# Placa_ATMEL_2019_v2_4.net
KiCad netlist of a schematic drawn in EAGLE
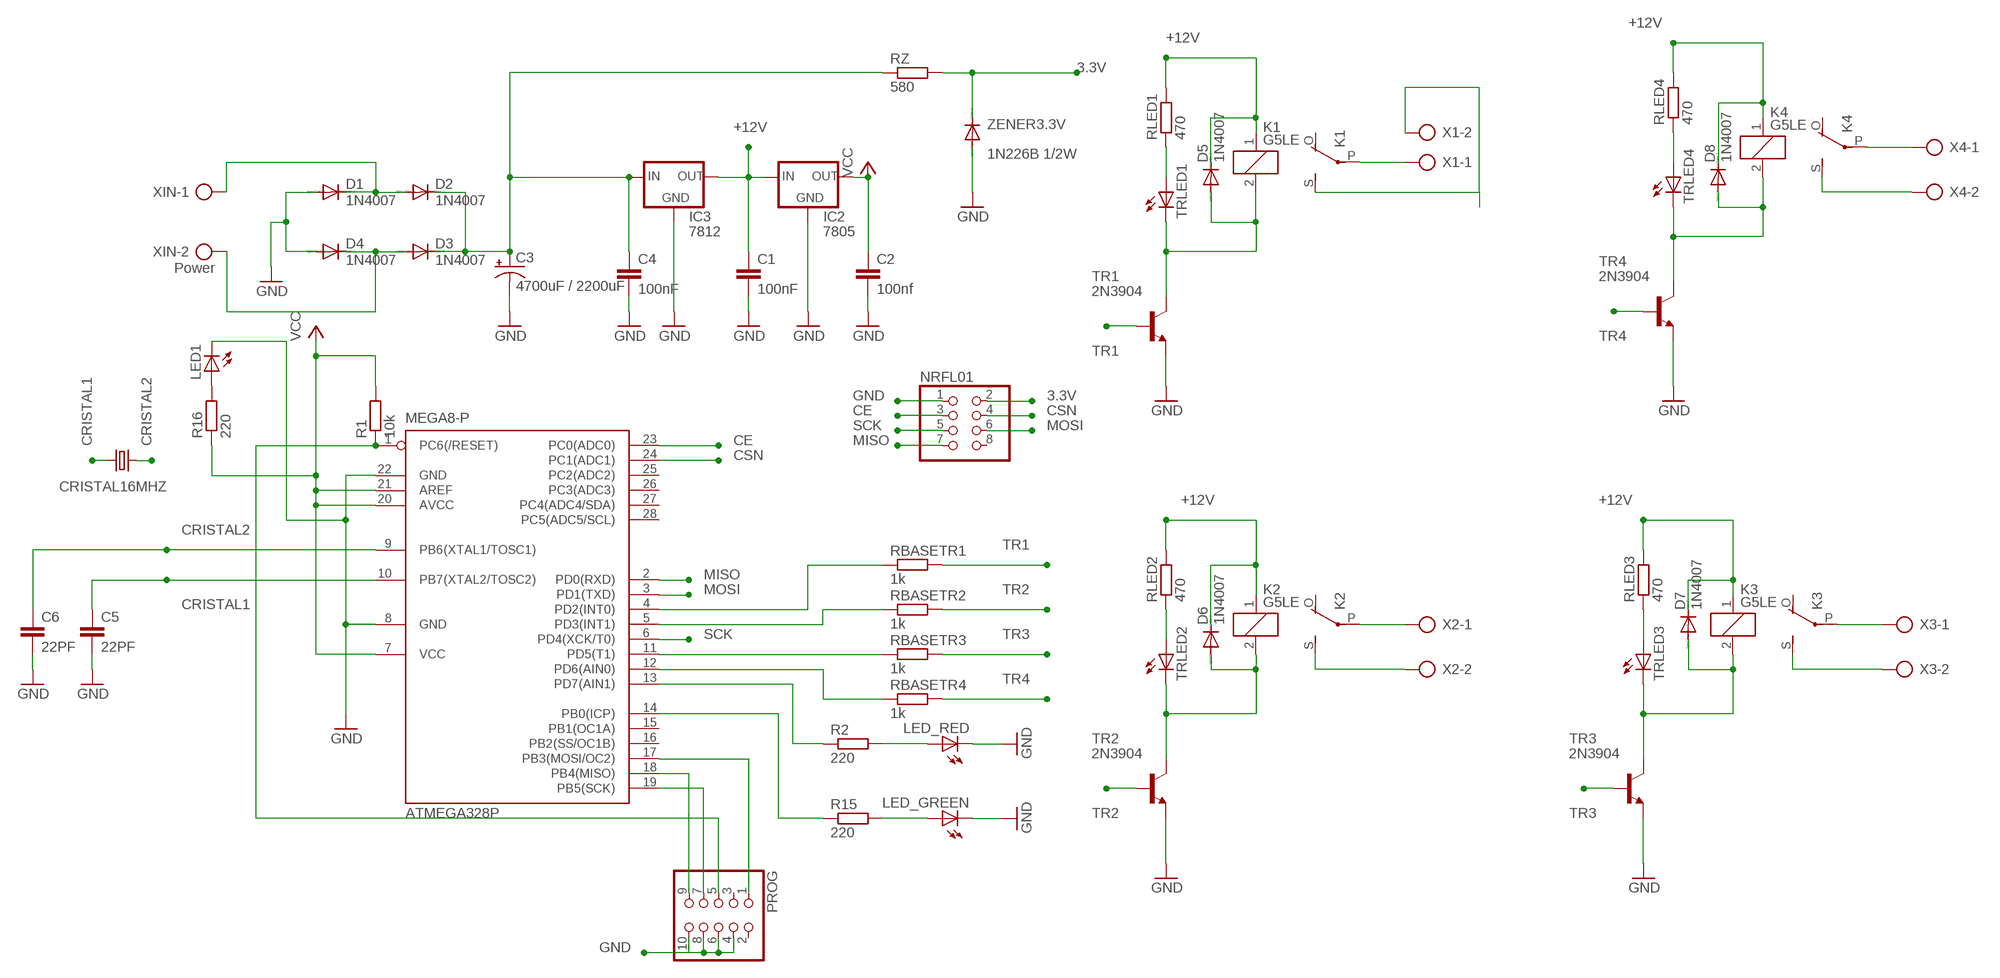
[diagram p0: schematic, sheet 1]

(export (version "E")
  (design (tool "Eeschema 10.0.6"))
  (components
    (comp (ref "ATMEGA328P")
      (value "MEGA8-P")
      (footprint "eagle-import:DIL28-3")
      (libsource (lib "eagle-import") (part "MEGA8-P"))
    )
    (comp (ref "C1")
      (value "100nF")
      (footprint "eagle-import:C050-025X075")
      (libsource (lib "eagle-import") (part "C-EU050-025X075"))
    )
    (comp (ref "C2")
      (value "100nf")
      (footprint "eagle-import:C050-025X075")
      (libsource (lib "eagle-import") (part "C-EU050-025X075"))
    )
    (comp (ref "C3")
      (value "4700uF / 2200uF")
      (footprint "eagle-import:E7,5-16")
      (libsource (lib "eagle-import") (part "CPOL-USE7.5-16"))
    )
    (comp (ref "C4")
      (value "100nF")
      (footprint "eagle-import:C050-025X075")
      (libsource (lib "eagle-import") (part "C-EU050-025X075"))
    )
    (comp (ref "C5")
      (value "22PF")
      (footprint "eagle-import:C050-024X044")
      (libsource (lib "eagle-import") (part "C-EU050-024X044"))
    )
    (comp (ref "C6")
      (value "22PF")
      (footprint "eagle-import:C050-024X044")
      (libsource (lib "eagle-import") (part "C-EU050-024X044"))
    )
    (comp (ref "CRISTAL16MHZ")
      (value "CRYSTALHC49S")
      (footprint "eagle-import:HC49_S")
      (libsource (lib "eagle-import") (part "CRYSTALHC49S"))
    )
    (comp (ref "D1")
      (value "1N4007")
      (footprint "eagle-import:DO41-10")
      (libsource (lib "eagle-import") (part "1N4004"))
    )
    (comp (ref "D2")
      (value "1N4007")
      (footprint "eagle-import:DO41-10")
      (libsource (lib "eagle-import") (part "1N4004"))
    )
    (comp (ref "D3")
      (value "1N4007")
      (footprint "eagle-import:DO41-10")
      (libsource (lib "eagle-import") (part "1N4004"))
    )
    (comp (ref "D4")
      (value "1N4007")
      (footprint "eagle-import:DO41-10")
      (libsource (lib "eagle-import") (part "1N4004"))
    )
    (comp (ref "D5")
      (value "1N4007")
      (footprint "eagle-import:DO41-10")
      (libsource (lib "eagle-import") (part "1N4004"))
    )
    (comp (ref "D6")
      (value "1N4007")
      (footprint "eagle-import:DO41-10")
      (libsource (lib "eagle-import") (part "1N4004"))
    )
    (comp (ref "D7")
      (value "1N4007")
      (footprint "eagle-import:DO41-10")
      (libsource (lib "eagle-import") (part "1N4004"))
    )
    (comp (ref "D8")
      (value "1N4007")
      (footprint "eagle-import:DO41-10")
      (libsource (lib "eagle-import") (part "1N4004"))
    )
    (comp (ref "IC2")
      (value "7805")
      (footprint "eagle-import:78XXL")
      (libsource (lib "eagle-import") (part "78XXL"))
    )
    (comp (ref "IC3")
      (value "7812")
      (footprint "eagle-import:78XXL")
      (libsource (lib "eagle-import") (part "78XXL"))
    )
    (comp (ref "K1")
      (value "G5LE")
      (footprint "eagle-import:G5LE")
      (libsource (lib "eagle-import") (part "G5LE"))
    )
    (comp (ref "K2")
      (value "G5LE")
      (footprint "eagle-import:G5LE")
      (libsource (lib "eagle-import") (part "G5LE"))
    )
    (comp (ref "K3")
      (value "G5LE")
      (footprint "eagle-import:G5LE")
      (libsource (lib "eagle-import") (part "G5LE"))
    )
    (comp (ref "K4")
      (value "G5LE")
      (footprint "eagle-import:G5LE")
      (libsource (lib "eagle-import") (part "G5LE"))
    )
    (comp (ref "LED1")
      (value "LED5MM")
      (footprint "eagle-import:LED5MM")
      (libsource (lib "eagle-import") (part "LED5MM"))
    )
    (comp (ref "LED_GREEN")
      (value "LED5MM")
      (footprint "eagle-import:LED5MM")
      (libsource (lib "eagle-import") (part "LED5MM"))
    )
    (comp (ref "LED_RED")
      (value "LED5MM")
      (footprint "eagle-import:LED5MM")
      (libsource (lib "eagle-import") (part "LED5MM"))
    )
    (comp (ref "NRFL01")
      (value "PINHD-2X4")
      (footprint "eagle-import:2X04")
      (libsource (lib "eagle-import") (part "PINHD-2X4"))
    )
    (comp (ref "PROG")
      (value "PINHD-2X5")
      (footprint "eagle-import:2X05")
      (libsource (lib "eagle-import") (part "PINHD-2X5"))
    )
    (comp (ref "R1")
      (value "10k")
      (footprint "eagle-import:0207_10")
      (libsource (lib "eagle-import") (part "R-EU_0207/10"))
    )
    (comp (ref "R2")
      (value "220")
      (footprint "eagle-import:0207_10")
      (libsource (lib "eagle-import") (part "R-EU_0207/10"))
    )
    (comp (ref "R15")
      (value "220")
      (footprint "eagle-import:0207_10")
      (libsource (lib "eagle-import") (part "R-EU_0207/10"))
    )
    (comp (ref "R16")
      (value "220")
      (footprint "eagle-import:0309_10")
      (libsource (lib "eagle-import") (part "R-EU_0309/10"))
    )
    (comp (ref "RBASETR1")
      (value "1k")
      (footprint "eagle-import:0207_10")
      (libsource (lib "eagle-import") (part "R-EU_0207/10"))
    )
    (comp (ref "RBASETR2")
      (value "1k")
      (footprint "eagle-import:0207_10")
      (libsource (lib "eagle-import") (part "R-EU_0207/10"))
    )
    (comp (ref "RBASETR3")
      (value "1k")
      (footprint "eagle-import:0204_7")
      (libsource (lib "eagle-import") (part "R-EU_0204/7"))
    )
    (comp (ref "RBASETR4")
      (value "1k")
      (footprint "eagle-import:0207_15")
      (libsource (lib "eagle-import") (part "R-EU_0207/15"))
    )
    (comp (ref "RLED1")
      (value "470")
      (footprint "eagle-import:0207_10")
      (libsource (lib "eagle-import") (part "R-EU_0207/10"))
    )
    (comp (ref "RLED2")
      (value "470")
      (footprint "eagle-import:0207_10")
      (libsource (lib "eagle-import") (part "R-EU_0207/10"))
    )
    (comp (ref "RLED3")
      (value "470")
      (footprint "eagle-import:0207_10")
      (libsource (lib "eagle-import") (part "R-EU_0207/10"))
    )
    (comp (ref "RLED4")
      (value "470")
      (footprint "eagle-import:0207_10")
      (libsource (lib "eagle-import") (part "R-EU_0207/10"))
    )
    (comp (ref "RZ")
      (value "580")
      (footprint "eagle-import:0207_10")
      (libsource (lib "eagle-import") (part "R-EU_0207/10"))
    )
    (comp (ref "TR1")
      (value "2N3904")
      (footprint "eagle-import:TO92")
      (libsource (lib "eagle-import") (part "2N3904"))
    )
    (comp (ref "TR2")
      (value "2N3904")
      (footprint "eagle-import:TO92")
      (libsource (lib "eagle-import") (part "2N3904"))
    )
    (comp (ref "TR3")
      (value "2N3904")
      (footprint "eagle-import:TO92")
      (libsource (lib "eagle-import") (part "2N3904"))
    )
    (comp (ref "TR4")
      (value "2N3904")
      (footprint "eagle-import:TO92")
      (libsource (lib "eagle-import") (part "2N3904"))
    )
    (comp (ref "TRLED1")
      (value "LED5MM")
      (footprint "eagle-import:LED5MM")
      (libsource (lib "eagle-import") (part "LED5MM"))
    )
    (comp (ref "TRLED2")
      (value "LED5MM")
      (footprint "eagle-import:LED5MM")
      (libsource (lib "eagle-import") (part "LED5MM"))
    )
    (comp (ref "TRLED3")
      (value "LED5MM")
      (footprint "eagle-import:LED5MM")
      (libsource (lib "eagle-import") (part "LED5MM"))
    )
    (comp (ref "TRLED4")
      (value "LED5MM")
      (footprint "eagle-import:LED5MM")
      (libsource (lib "eagle-import") (part "LED5MM"))
    )
    (comp (ref "X1")
      (value "AK300/2")
      (footprint "eagle-import:AK300_2")
      (libsource (lib "eagle-import") (part "AK300/2"))
    )
    (comp (ref "X2")
      (value "AK300/2")
      (footprint "eagle-import:AK300_2")
      (libsource (lib "eagle-import") (part "AK300/2"))
    )
    (comp (ref "X3")
      (value "AK300/2")
      (footprint "eagle-import:AK300_2")
      (libsource (lib "eagle-import") (part "AK300/2"))
    )
    (comp (ref "X4")
      (value "AK300/2")
      (footprint "eagle-import:AK300_2")
      (libsource (lib "eagle-import") (part "AK300/2"))
    )
    (comp (ref "XIN")
      (value "Power")
      (footprint "eagle-import:AK500_2")
      (libsource (lib "eagle-import") (part "AK500/2"))
    )
    (comp (ref "ZENER3.3V")
      (value "1N226B 1/2W")
      (footprint "eagle-import:DO35-10")
      (libsource (lib "eagle-import") (part "1N4148DO35-10"))
    )
  )
  (nets
    (net (code "1") (name "/+12V") (class "Default")
      (node (ref "C1") (pin "1") (pinfunction "1_1") (pintype "passive"))
      (node (ref "D5") (pin "C") (pinfunction "C_C") (pintype "passive"))
      (node (ref "D6") (pin "C") (pinfunction "C_C") (pintype "passive"))
      (node (ref "D7") (pin "C") (pinfunction "C_C") (pintype "passive"))
      (node (ref "D8") (pin "C") (pinfunction "C_C") (pintype "passive"))
      (node (ref "IC2") (pin "IN") (pinfunction "IN_IN") (pintype "input"))
      (node (ref "IC3") (pin "OUT") (pinfunction "OUT_OUT") (pintype "passive"))
      (node (ref "K1") (pin "1") (pinfunction "1_1") (pintype "passive"))
      (node (ref "K2") (pin "1") (pinfunction "1_1") (pintype "passive"))
      (node (ref "K3") (pin "1") (pinfunction "1_1") (pintype "passive"))
      (node (ref "K4") (pin "1") (pinfunction "1_1") (pintype "passive"))
      (node (ref "RLED1") (pin "2") (pinfunction "2_2") (pintype "passive"))
      (node (ref "RLED2") (pin "2") (pinfunction "2_2") (pintype "passive"))
      (node (ref "RLED3") (pin "2") (pinfunction "2_2") (pintype "passive"))
      (node (ref "RLED4") (pin "2") (pinfunction "2_2") (pintype "passive"))
    )
    (net (code "2") (name "/3.3V") (class "Default")
      (node (ref "NRFL01") (pin "2") (pinfunction "2_2") (pintype "passive"))
      (node (ref "RZ") (pin "2") (pinfunction "2_2") (pintype "passive"))
      (node (ref "ZENER3.3V") (pin "C") (pinfunction "C_C") (pintype "passive"))
    )
    (net (code "3") (name "/CE") (class "Default")
      (node (ref "ATMEGA328P") (pin "23") (pinfunction "PC0(ADC0)_23") (pintype "bidirectional"))
      (node (ref "NRFL01") (pin "3") (pinfunction "3_3") (pintype "passive"))
    )
    (net (code "4") (name "/CRISTAL1") (class "Default")
      (node (ref "ATMEGA328P") (pin "10") (pinfunction "PB7(XTAL2/TOSC2)_10") (pintype "bidirectional"))
      (node (ref "C5") (pin "1") (pinfunction "1_1") (pintype "passive"))
      (node (ref "CRISTAL16MHZ") (pin "2") (pinfunction "2_2") (pintype "passive"))
    )
    (net (code "5") (name "/CRISTAL2") (class "Default")
      (node (ref "ATMEGA328P") (pin "9") (pinfunction "PB6(XTAL1/TOSC1)_9") (pintype "bidirectional"))
      (node (ref "C6") (pin "1") (pinfunction "1_1") (pintype "passive"))
      (node (ref "CRISTAL16MHZ") (pin "1") (pinfunction "1_1") (pintype "passive"))
    )
    (net (code "6") (name "/CSN") (class "Default")
      (node (ref "ATMEGA328P") (pin "24") (pinfunction "PC1(ADC1)_24") (pintype "bidirectional"))
      (node (ref "NRFL01") (pin "4") (pinfunction "4_4") (pintype "passive"))
    )
    (net (code "7") (name "/MISO") (class "Default")
      (node (ref "ATMEGA328P") (pin "2") (pinfunction "PD0(RXD)_2") (pintype "bidirectional"))
      (node (ref "NRFL01") (pin "7") (pinfunction "7_7") (pintype "passive"))
    )
    (net (code "8") (name "/MOSI") (class "Default")
      (node (ref "ATMEGA328P") (pin "3") (pinfunction "PD1(TXD)_3") (pintype "bidirectional"))
      (node (ref "NRFL01") (pin "6") (pinfunction "6_6") (pintype "passive"))
    )
    (net (code "9") (name "/SCK") (class "Default")
      (node (ref "ATMEGA328P") (pin "6") (pinfunction "PD4(XCK/T0)_6") (pintype "bidirectional"))
      (node (ref "NRFL01") (pin "5") (pinfunction "5_5") (pintype "passive"))
    )
    (net (code "10") (name "/TR1") (class "Default")
      (node (ref "RBASETR1") (pin "2") (pinfunction "2_2") (pintype "passive"))
      (node (ref "TR1") (pin "2") (pinfunction "B_2") (pintype "passive"))
    )
    (net (code "11") (name "/TR2") (class "Default")
      (node (ref "RBASETR2") (pin "2") (pinfunction "2_2") (pintype "passive"))
      (node (ref "TR2") (pin "2") (pinfunction "B_2") (pintype "passive"))
    )
    (net (code "12") (name "/TR3") (class "Default")
      (node (ref "RBASETR3") (pin "2") (pinfunction "2_2") (pintype "passive"))
      (node (ref "TR3") (pin "2") (pinfunction "B_2") (pintype "passive"))
    )
    (net (code "13") (name "/TR4") (class "Default")
      (node (ref "RBASETR4") (pin "2") (pinfunction "2_2") (pintype "passive"))
      (node (ref "TR4") (pin "2") (pinfunction "B_2") (pintype "passive"))
    )
    (net (code "14") (name "GND") (class "Default")
      (node (ref "ATMEGA328P") (pin "22") (pinfunction "GND_22") (pintype "power_in"))
      (node (ref "ATMEGA328P") (pin "8") (pinfunction "GND_8") (pintype "power_in"))
      (node (ref "C1") (pin "2") (pinfunction "2_2") (pintype "passive"))
      (node (ref "C2") (pin "2") (pinfunction "2_2") (pintype "passive"))
      (node (ref "C3") (pin "-") (pinfunction "-_-") (pintype "passive"))
      (node (ref "C4") (pin "2") (pinfunction "2_2") (pintype "passive"))
      (node (ref "C5") (pin "2") (pinfunction "2_2") (pintype "passive"))
      (node (ref "C6") (pin "2") (pinfunction "2_2") (pintype "passive"))
      (node (ref "D1") (pin "A") (pinfunction "A_A") (pintype "passive"))
      (node (ref "D4") (pin "A") (pinfunction "A_A") (pintype "passive"))
      (node (ref "IC2") (pin "GND") (pinfunction "GND_GND") (pintype "input"))
      (node (ref "IC3") (pin "GND") (pinfunction "GND_GND") (pintype "input"))
      (node (ref "LED1") (pin "K") (pinfunction "C_K") (pintype "passive"))
      (node (ref "LED_GREEN") (pin "K") (pinfunction "C_K") (pintype "passive"))
      (node (ref "LED_RED") (pin "K") (pinfunction "C_K") (pintype "passive"))
      (node (ref "NRFL01") (pin "1") (pinfunction "1_1") (pintype "passive"))
      (node (ref "PROG") (pin "10") (pinfunction "10_10") (pintype "passive"))
      (node (ref "PROG") (pin "4") (pinfunction "4_4") (pintype "passive"))
      (node (ref "PROG") (pin "6") (pinfunction "6_6") (pintype "passive"))
      (node (ref "PROG") (pin "8") (pinfunction "8_8") (pintype "passive"))
      (node (ref "TR1") (pin "3") (pinfunction "E_3") (pintype "passive"))
      (node (ref "TR2") (pin "3") (pinfunction "E_3") (pintype "passive"))
      (node (ref "TR3") (pin "3") (pinfunction "E_3") (pintype "passive"))
      (node (ref "TR4") (pin "3") (pinfunction "E_3") (pintype "passive"))
      (node (ref "ZENER3.3V") (pin "A") (pinfunction "A_A") (pintype "passive"))
    )
    (net (code "15") (name "Net-(ATMEGA328P-PB0(ICP))") (class "Default")
      (node (ref "ATMEGA328P") (pin "14") (pinfunction "PB0(ICP)_14") (pintype "bidirectional"))
      (node (ref "R15") (pin "1") (pinfunction "1_1") (pintype "passive"))
    )
    (net (code "16") (name "Net-(ATMEGA328P-PB3(MOSI{slash}OC2))") (class "Default")
      (node (ref "ATMEGA328P") (pin "17") (pinfunction "PB3(MOSI/OC2)_17") (pintype "bidirectional"))
      (node (ref "PROG") (pin "1") (pinfunction "1_1") (pintype "passive"))
    )
    (net (code "17") (name "Net-(ATMEGA328P-PB4(MISO))") (class "Default")
      (node (ref "ATMEGA328P") (pin "18") (pinfunction "PB4(MISO)_18") (pintype "bidirectional"))
      (node (ref "PROG") (pin "9") (pinfunction "9_9") (pintype "passive"))
    )
    (net (code "18") (name "Net-(ATMEGA328P-PB5(SCK))") (class "Default")
      (node (ref "ATMEGA328P") (pin "19") (pinfunction "PB5(SCK)_19") (pintype "bidirectional"))
      (node (ref "PROG") (pin "7") (pinfunction "7_7") (pintype "passive"))
    )
    (net (code "19") (name "Net-(ATMEGA328P-PC6({slash}RESET))") (class "Default")
      (node (ref "ATMEGA328P") (pin "1") (pinfunction "PC6(/RESET)_1") (pintype "bidirectional"))
      (node (ref "PROG") (pin "5") (pinfunction "5_5") (pintype "passive"))
      (node (ref "R1") (pin "1") (pinfunction "1_1") (pintype "passive"))
    )
    (net (code "20") (name "Net-(ATMEGA328P-PD2(INT0))") (class "Default")
      (node (ref "ATMEGA328P") (pin "4") (pinfunction "PD2(INT0)_4") (pintype "bidirectional"))
      (node (ref "RBASETR1") (pin "1") (pinfunction "1_1") (pintype "passive"))
    )
    (net (code "21") (name "Net-(ATMEGA328P-PD3(INT1))") (class "Default")
      (node (ref "ATMEGA328P") (pin "5") (pinfunction "PD3(INT1)_5") (pintype "bidirectional"))
      (node (ref "RBASETR2") (pin "1") (pinfunction "1_1") (pintype "passive"))
    )
    (net (code "22") (name "Net-(ATMEGA328P-PD5(T1))") (class "Default")
      (node (ref "ATMEGA328P") (pin "11") (pinfunction "PD5(T1)_11") (pintype "bidirectional"))
      (node (ref "RBASETR3") (pin "1") (pinfunction "1_1") (pintype "passive"))
    )
    (net (code "23") (name "Net-(ATMEGA328P-PD6(AIN0))") (class "Default")
      (node (ref "ATMEGA328P") (pin "12") (pinfunction "PD6(AIN0)_12") (pintype "bidirectional"))
      (node (ref "RBASETR4") (pin "1") (pinfunction "1_1") (pintype "passive"))
    )
    (net (code "24") (name "Net-(ATMEGA328P-PD7(AIN1))") (class "Default")
      (node (ref "ATMEGA328P") (pin "13") (pinfunction "PD7(AIN1)_13") (pintype "bidirectional"))
      (node (ref "R2") (pin "1") (pinfunction "1_1") (pintype "passive"))
    )
    (net (code "25") (name "Net-(C3-Pad+)") (class "Default")
      (node (ref "C3") (pin "+") (pinfunction "+_+") (pintype "passive"))
      (node (ref "C4") (pin "1") (pinfunction "1_1") (pintype "passive"))
      (node (ref "D2") (pin "C") (pinfunction "C_C") (pintype "passive"))
      (node (ref "D3") (pin "C") (pinfunction "C_C") (pintype "passive"))
      (node (ref "IC3") (pin "IN") (pinfunction "IN_IN") (pintype "input"))
      (node (ref "RZ") (pin "1") (pinfunction "1_1") (pintype "passive"))
    )
    (net (code "26") (name "Net-(LED1-PadA)") (class "Default")
      (node (ref "LED1") (pin "A") (pinfunction "A_A") (pintype "passive"))
      (node (ref "R16") (pin "2") (pinfunction "2_2") (pintype "passive"))
    )
    (net (code "27") (name "Net-(LED_GREEN-PadA)") (class "Default")
      (node (ref "LED_GREEN") (pin "A") (pinfunction "A_A") (pintype "passive"))
      (node (ref "R15") (pin "2") (pinfunction "2_2") (pintype "passive"))
    )
    (net (code "28") (name "Net-(LED_RED-PadA)") (class "Default")
      (node (ref "LED_RED") (pin "A") (pinfunction "A_A") (pintype "passive"))
      (node (ref "R2") (pin "2") (pinfunction "2_2") (pintype "passive"))
    )
    (net (code "29") (name "Net-(RLED1-Pad1)") (class "Default")
      (node (ref "RLED1") (pin "1") (pinfunction "1_1") (pintype "passive"))
      (node (ref "TRLED1") (pin "A") (pinfunction "A_A") (pintype "passive"))
    )
    (net (code "30") (name "Net-(RLED2-Pad1)") (class "Default")
      (node (ref "RLED2") (pin "1") (pinfunction "1_1") (pintype "passive"))
      (node (ref "TRLED2") (pin "A") (pinfunction "A_A") (pintype "passive"))
    )
    (net (code "31") (name "Net-(RLED3-Pad1)") (class "Default")
      (node (ref "RLED3") (pin "1") (pinfunction "1_1") (pintype "passive"))
      (node (ref "TRLED3") (pin "A") (pinfunction "A_A") (pintype "passive"))
    )
    (net (code "32") (name "Net-(RLED4-Pad1)") (class "Default")
      (node (ref "RLED4") (pin "1") (pinfunction "1_1") (pintype "passive"))
      (node (ref "TRLED4") (pin "A") (pinfunction "A_A") (pintype "passive"))
    )
    (net (code "33") (name "Net-(TR1-C)") (class "Default")
      (node (ref "D5") (pin "A") (pinfunction "A_A") (pintype "passive"))
      (node (ref "K1") (pin "2") (pinfunction "2_2") (pintype "passive"))
      (node (ref "TR1") (pin "1") (pinfunction "C_1") (pintype "passive"))
      (node (ref "TRLED1") (pin "K") (pinfunction "C_K") (pintype "passive"))
    )
    (net (code "34") (name "Net-(TR2-C)") (class "Default")
      (node (ref "D6") (pin "A") (pinfunction "A_A") (pintype "passive"))
      (node (ref "K2") (pin "2") (pinfunction "2_2") (pintype "passive"))
      (node (ref "TR2") (pin "1") (pinfunction "C_1") (pintype "passive"))
      (node (ref "TRLED2") (pin "K") (pinfunction "C_K") (pintype "passive"))
    )
    (net (code "35") (name "Net-(TR3-C)") (class "Default")
      (node (ref "D7") (pin "A") (pinfunction "A_A") (pintype "passive"))
      (node (ref "K3") (pin "2") (pinfunction "2_2") (pintype "passive"))
      (node (ref "TR3") (pin "1") (pinfunction "C_1") (pintype "passive"))
      (node (ref "TRLED3") (pin "K") (pinfunction "C_K") (pintype "passive"))
    )
    (net (code "36") (name "Net-(TR4-C)") (class "Default")
      (node (ref "D8") (pin "A") (pinfunction "A_A") (pintype "passive"))
      (node (ref "K4") (pin "2") (pinfunction "2_2") (pintype "passive"))
      (node (ref "TR4") (pin "1") (pinfunction "C_1") (pintype "passive"))
      (node (ref "TRLED4") (pin "K") (pinfunction "C_K") (pintype "passive"))
    )
    (net (code "37") (name "Net-(X1A-KL)") (class "Default")
      (node (ref "K1") (pin "P") (pinfunction "P_P") (pintype "passive"))
      (node (ref "X1") (pin "1") (pinfunction "KL_1") (pintype "passive"))
    )
    (net (code "38") (name "Net-(X1B-KL)") (class "Default")
      (node (ref "K1") (pin "S") (pinfunction "S_S") (pintype "passive"))
      (node (ref "X1") (pin "2") (pinfunction "KL_2") (pintype "passive"))
    )
    (net (code "39") (name "Net-(X2A-KL)") (class "Default")
      (node (ref "K2") (pin "P") (pinfunction "P_P") (pintype "passive"))
      (node (ref "X2") (pin "1") (pinfunction "KL_1") (pintype "passive"))
    )
    (net (code "40") (name "Net-(X2B-KL)") (class "Default")
      (node (ref "K2") (pin "S") (pinfunction "S_S") (pintype "passive"))
      (node (ref "X2") (pin "2") (pinfunction "KL_2") (pintype "passive"))
    )
    (net (code "41") (name "Net-(X3A-KL)") (class "Default")
      (node (ref "K3") (pin "P") (pinfunction "P_P") (pintype "passive"))
      (node (ref "X3") (pin "1") (pinfunction "KL_1") (pintype "passive"))
    )
    (net (code "42") (name "Net-(X3B-KL)") (class "Default")
      (node (ref "K3") (pin "S") (pinfunction "S_S") (pintype "passive"))
      (node (ref "X3") (pin "2") (pinfunction "KL_2") (pintype "passive"))
    )
    (net (code "43") (name "Net-(X4A-KL)") (class "Default")
      (node (ref "K4") (pin "P") (pinfunction "P_P") (pintype "passive"))
      (node (ref "X4") (pin "1") (pinfunction "KL_1") (pintype "passive"))
    )
    (net (code "44") (name "Net-(X4B-KL)") (class "Default")
      (node (ref "K4") (pin "S") (pinfunction "S_S") (pintype "passive"))
      (node (ref "X4") (pin "2") (pinfunction "KL_2") (pintype "passive"))
    )
    (net (code "45") (name "Net-(XINA-KL)") (class "Default")
      (node (ref "D1") (pin "C") (pinfunction "C_C") (pintype "passive"))
      (node (ref "D2") (pin "A") (pinfunction "A_A") (pintype "passive"))
      (node (ref "XIN") (pin "1") (pinfunction "KL_1") (pintype "passive"))
    )
    (net (code "46") (name "Net-(XINB-KL)") (class "Default")
      (node (ref "D3") (pin "A") (pinfunction "A_A") (pintype "passive"))
      (node (ref "D4") (pin "C") (pinfunction "C_C") (pintype "passive"))
      (node (ref "XIN") (pin "2") (pinfunction "KL_2") (pintype "passive"))
    )
    (net (code "47") (name "VCC") (class "Default")
      (node (ref "ATMEGA328P") (pin "20") (pinfunction "AVCC_20") (pintype "power_in"))
      (node (ref "ATMEGA328P") (pin "21") (pinfunction "AREF_21") (pintype "passive"))
      (node (ref "ATMEGA328P") (pin "7") (pinfunction "VCC_7") (pintype "power_in"))
      (node (ref "C2") (pin "1") (pinfunction "1_1") (pintype "passive"))
      (node (ref "IC2") (pin "OUT") (pinfunction "OUT_OUT") (pintype "passive"))
      (node (ref "R1") (pin "2") (pinfunction "2_2") (pintype "passive"))
      (node (ref "R16") (pin "1") (pinfunction "1_1") (pintype "passive"))
    )
    (net (code "48") (name "unconnected-(ATMEGA328P-PB1(OC1A)-Pad15)") (class "Default")
      (node (ref "ATMEGA328P") (pin "15") (pinfunction "PB1(OC1A)_15") (pintype "bidirectional"))
    )
    (net (code "49") (name "unconnected-(ATMEGA328P-PB2(SS{slash}OC1B)-Pad16)") (class "Default")
      (node (ref "ATMEGA328P") (pin "16") (pinfunction "PB2(SS/OC1B)_16") (pintype "bidirectional"))
    )
    (net (code "50") (name "unconnected-(ATMEGA328P-PC2(ADC2)-Pad25)") (class "Default")
      (node (ref "ATMEGA328P") (pin "25") (pinfunction "PC2(ADC2)_25") (pintype "bidirectional"))
    )
    (net (code "51") (name "unconnected-(ATMEGA328P-PC3(ADC3)-Pad26)") (class "Default")
      (node (ref "ATMEGA328P") (pin "26") (pinfunction "PC3(ADC3)_26") (pintype "bidirectional"))
    )
    (net (code "52") (name "unconnected-(ATMEGA328P-PC4(ADC4{slash}SDA)-Pad27)") (class "Default")
      (node (ref "ATMEGA328P") (pin "27") (pinfunction "PC4(ADC4/SDA)_27") (pintype "bidirectional"))
    )
    (net (code "53") (name "unconnected-(ATMEGA328P-PC5(ADC5{slash}SCL)-Pad28)") (class "Default")
      (node (ref "ATMEGA328P") (pin "28") (pinfunction "PC5(ADC5/SCL)_28") (pintype "bidirectional"))
    )
    (net (code "54") (name "unconnected-(K1-PadO)") (class "Default")
      (node (ref "K1") (pin "O") (pinfunction "O_O") (pintype "passive"))
    )
    (net (code "55") (name "unconnected-(K2-PadO)") (class "Default")
      (node (ref "K2") (pin "O") (pinfunction "O_O") (pintype "passive"))
    )
    (net (code "56") (name "unconnected-(K3-PadO)") (class "Default")
      (node (ref "K3") (pin "O") (pinfunction "O_O") (pintype "passive"))
    )
    (net (code "57") (name "unconnected-(K4-PadO)") (class "Default")
      (node (ref "K4") (pin "O") (pinfunction "O_O") (pintype "passive"))
    )
    (net (code "58") (name "unconnected-(NRFL01-Pad8)") (class "Default")
      (node (ref "NRFL01") (pin "8") (pinfunction "8_8") (pintype "passive"))
    )
    (net (code "59") (name "unconnected-(PROG-Pad2)") (class "Default")
      (node (ref "PROG") (pin "2") (pinfunction "2_2") (pintype "passive"))
    )
    (net (code "60") (name "unconnected-(PROG-Pad3)") (class "Default")
      (node (ref "PROG") (pin "3") (pinfunction "3_3") (pintype "passive"))
    )
  )
)
